# Stimulation_Stage.net
KiCad netlist of a schematic drawn in Altium Designer
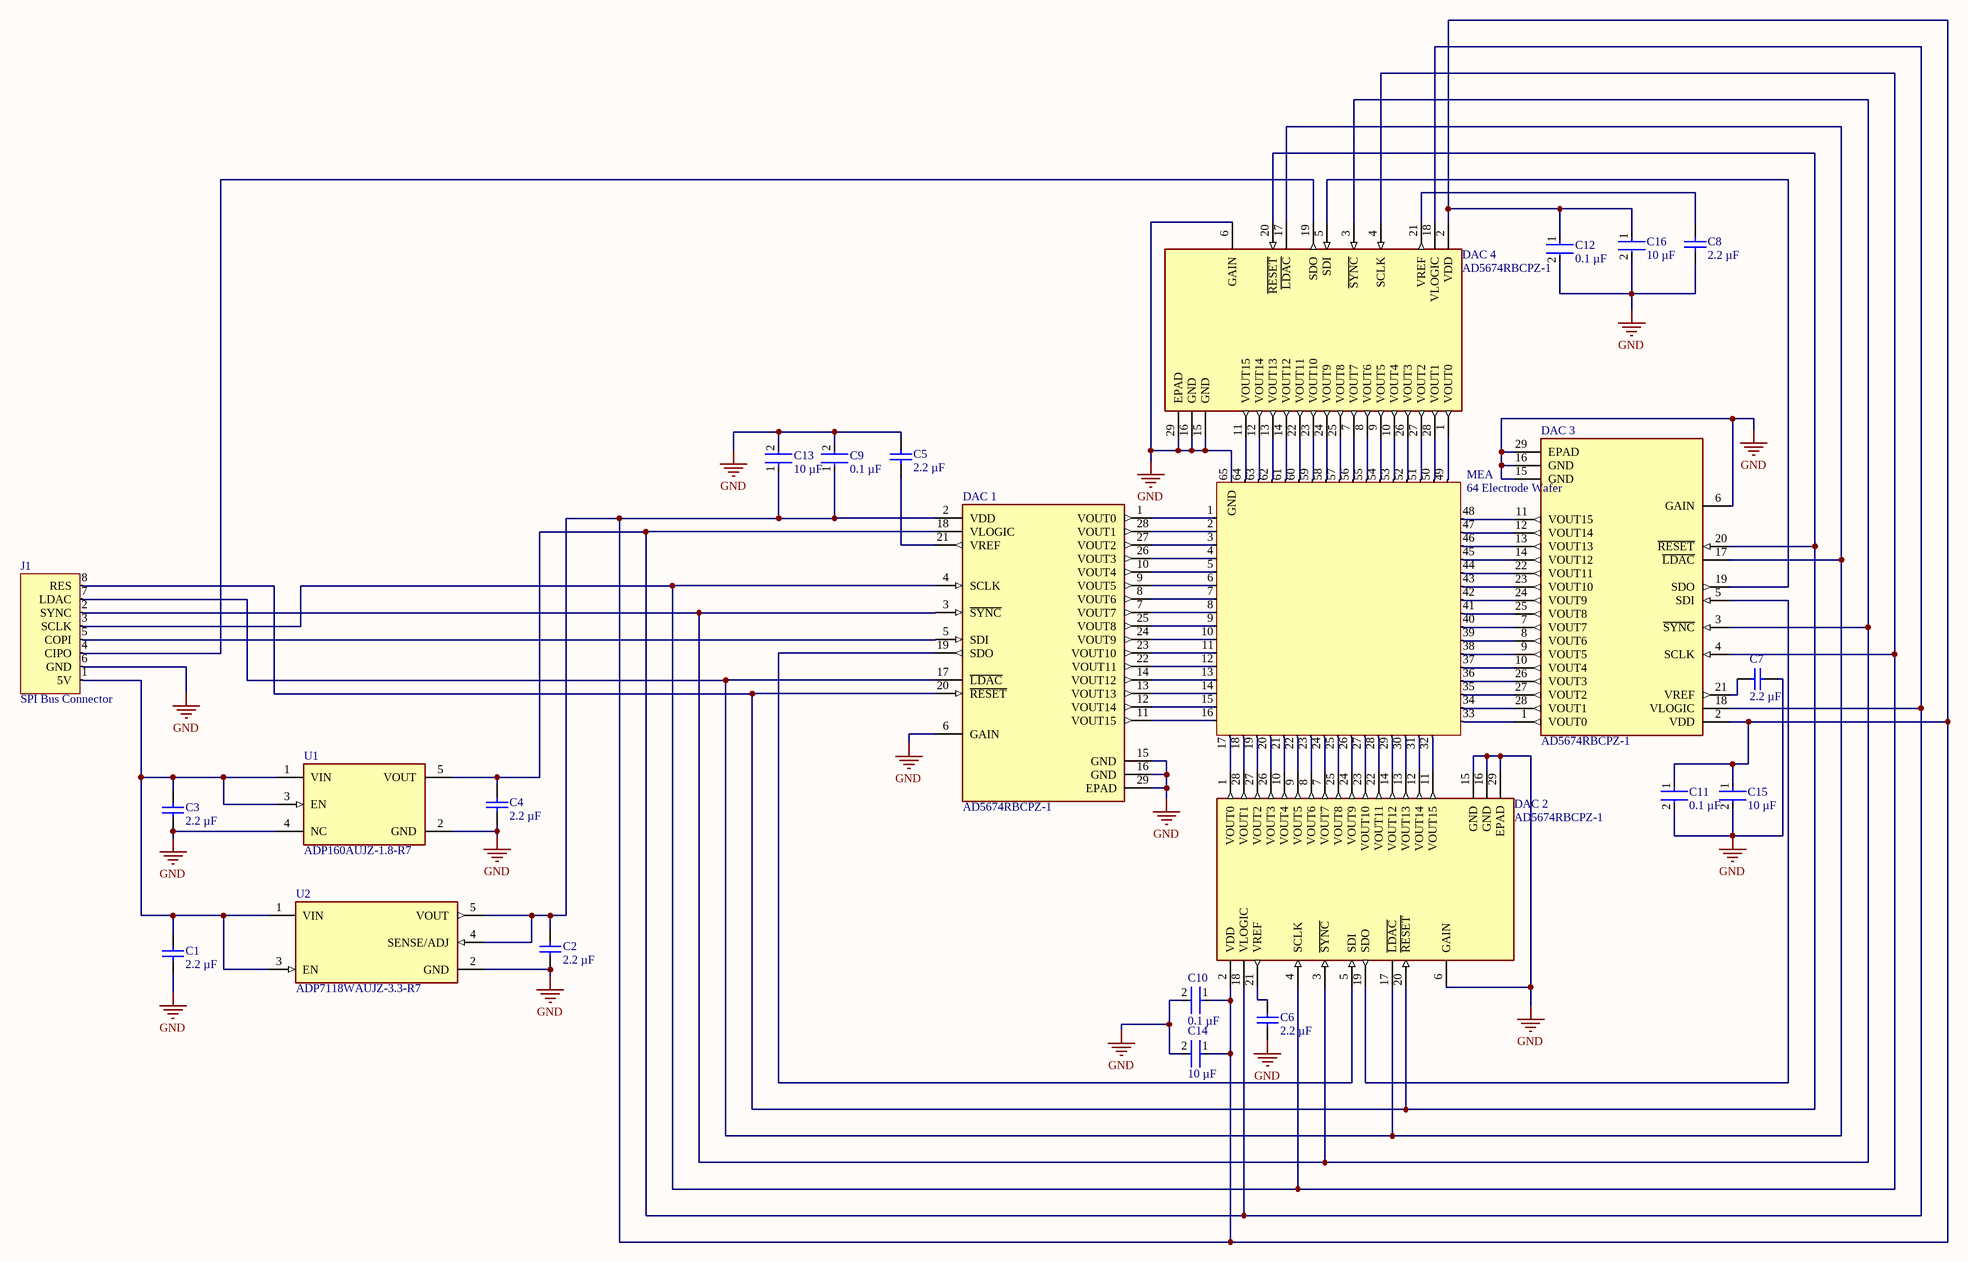
[diagram p0: Stimulation Stage.SchDoc]

(export (version "E")
  (design (tool "Eeschema 10.0.6"))
  (components
    (comp (ref "C1")
      (value "2.2 µF")
      (footprint "CAPC1608X90X30LL10T20")
      (description "Chip Capacitor, 2.2 uF, +/- 10%, 10 V, -55 to 85 degC, 0603 (1608 Metric), RoHS, Tape and Reel")
      (fields (field (name "MANUFACTURER") "Samsung Electro-Mechanics"))
      (libsource (lib "Altium Content Vault") (part "CAP-NP-2"))
    )
    (comp (ref "C2")
      (value "2.2 µF")
      (footprint "CAPC1608X90X30LL10T20")
      (description "Chip Capacitor, 2.2 uF, +/- 10%, 10 V, -55 to 85 degC, 0603 (1608 Metric), RoHS, Tape and Reel")
      (fields (field (name "MANUFACTURER") "Samsung Electro-Mechanics"))
      (libsource (lib "Altium Content Vault") (part "CAP-NP-2"))
    )
    (comp (ref "C3")
      (value "2.2 µF")
      (footprint "CAPC1608X90X30LL10T20")
      (description "Chip Capacitor, 2.2 uF, +/- 10%, 10 V, -55 to 85 degC, 0603 (1608 Metric), RoHS, Tape and Reel")
      (fields (field (name "MANUFACTURER") "Samsung Electro-Mechanics"))
      (libsource (lib "Altium Content Vault") (part "CAP-NP-2"))
    )
    (comp (ref "C4")
      (value "2.2 µF")
      (footprint "CAPC1608X90X30LL10T20")
      (description "Chip Capacitor, 2.2 uF, +/- 10%, 10 V, -55 to 85 degC, 0603 (1608 Metric), RoHS, Tape and Reel")
      (fields (field (name "MANUFACTURER") "Samsung Electro-Mechanics"))
      (libsource (lib "Altium Content Vault") (part "CAP-NP-2"))
    )
    (comp (ref "C5")
      (value "2.2 µF")
      (footprint "CAPC1608X90X30LL10T20")
      (description "Chip Capacitor, 2.2 uF, +/- 10%, 10 V, -55 to 85 degC, 0603 (1608 Metric), RoHS, Tape and Reel")
      (fields (field (name "MANUFACTURER") "Samsung Electro-Mechanics"))
      (libsource (lib "Altium Content Vault") (part "CAP-NP-2"))
    )
    (comp (ref "C6")
      (value "2.2 µF")
      (footprint "CAPC1608X90X30LL10T20")
      (description "Chip Capacitor, 2.2 uF, +/- 10%, 10 V, -55 to 85 degC, 0603 (1608 Metric), RoHS, Tape and Reel")
      (fields (field (name "MANUFACTURER") "Samsung Electro-Mechanics"))
      (libsource (lib "Altium Content Vault") (part "CAP-NP-2"))
    )
    (comp (ref "C7")
      (value "2.2 µF")
      (footprint "CAPC1608X90X30LL10T20")
      (description "Chip Capacitor, 2.2 uF, +/- 10%, 10 V, -55 to 85 degC, 0603 (1608 Metric), RoHS, Tape and Reel")
      (fields (field (name "MANUFACTURER") "Samsung Electro-Mechanics"))
      (libsource (lib "Altium Content Vault") (part "CAP-NP-2"))
    )
    (comp (ref "C8")
      (value "2.2 µF")
      (footprint "CAPC1608X90X30LL10T20")
      (description "Chip Capacitor, 2.2 uF, +/- 10%, 10 V, -55 to 85 degC, 0603 (1608 Metric), RoHS, Tape and Reel")
      (fields (field (name "MANUFACTURER") "Samsung Electro-Mechanics"))
      (libsource (lib "Altium Content Vault") (part "CAP-NP-2"))
    )
    (comp (ref "C9")
      (value "0.1 µF")
      (footprint "FP-CL278-IPC_C")
      (description "Cap Ceramic 100nF 25V X5R ±10% SMD 0402 +85°C Paper T/R")
      (fields (field (name "VOLTAGE") "25V") (field (name "TOLERANCE") "10%"))
      (libsource (lib "Altium Content Vault") (part "b4654b650e69147ec39a6b967a45e02"))
    )
    (comp (ref "C10")
      (value "0.1 µF")
      (footprint "FP-CL278-IPC_C")
      (description "Cap Ceramic 100nF 25V X5R ±10% SMD 0402 +85°C Paper T/R")
      (fields (field (name "VOLTAGE") "25V") (field (name "TOLERANCE") "10%"))
      (libsource (lib "Altium Content Vault") (part "b4654b650e69147ec39a6b967a45e02"))
    )
    (comp (ref "C11")
      (value "0.1 µF")
      (footprint "FP-CL278-IPC_C")
      (description "Cap Ceramic 100nF 25V X5R ±10% SMD 0402 +85°C Paper T/R")
      (fields (field (name "VOLTAGE") "25V") (field (name "TOLERANCE") "10%"))
      (libsource (lib "Altium Content Vault") (part "b4654b650e69147ec39a6b967a45e02"))
    )
    (comp (ref "C12")
      (value "0.1 µF")
      (footprint "FP-CL278-IPC_C")
      (description "Cap Ceramic 100nF 25V X5R ±10% SMD 0402 +85°C Paper T/R")
      (fields (field (name "VOLTAGE") "25V") (field (name "TOLERANCE") "10%"))
      (libsource (lib "Altium Content Vault") (part "b4654b650e69147ec39a6b967a45e02"))
    )
    (comp (ref "C13")
      (value "10 µF")
      (footprint "FP-CL10-IPC_C")
      (description "Cap Ceramic 10uF 6.3V X5R ±20% Pad SMD 0603 +85°C T/R")
      (fields (field (name "VOLTAGE") "6.3V") (field (name "TOLERANCE") "20%"))
      (libsource (lib "Altium Content Vault") (part "b4654b650e69147ec39a6b967a45e02"))
    )
    (comp (ref "C14")
      (value "10 µF")
      (footprint "FP-CL10-IPC_C")
      (description "Cap Ceramic 10uF 6.3V X5R ±20% Pad SMD 0603 +85°C T/R")
      (fields (field (name "VOLTAGE") "6.3V") (field (name "TOLERANCE") "20%"))
      (libsource (lib "Altium Content Vault") (part "b4654b650e69147ec39a6b967a45e02"))
    )
    (comp (ref "C15")
      (value "10 µF")
      (footprint "FP-CL10-IPC_C")
      (description "Cap Ceramic 10uF 6.3V X5R ±20% Pad SMD 0603 +85°C T/R")
      (fields (field (name "VOLTAGE") "6.3V") (field (name "TOLERANCE") "20%"))
      (libsource (lib "Altium Content Vault") (part "b4654b650e69147ec39a6b967a45e02"))
    )
    (comp (ref "C16")
      (value "10 µF")
      (footprint "FP-CL10-IPC_C")
      (description "Cap Ceramic 10uF 6.3V X5R ±20% Pad SMD 0603 +85°C T/R")
      (fields (field (name "VOLTAGE") "6.3V") (field (name "TOLERANCE") "20%"))
      (libsource (lib "Altium Content Vault") (part "b4654b650e69147ec39a6b967a45e02"))
    )
    (comp (ref "DAC 1")
      (value "AD5674RBCPZ-1")
      (footprint "FP-CP-28-9-IPC_C")
      (description "16-CH12-BITNANODAC+WITH2PPM/CREF")
      (libsource (lib "Altium Content Vault") (part "8444db3836bae7896dad1ad18e8f2a5"))
    )
    (comp (ref "DAC 2")
      (value "AD5674RBCPZ-1")
      (footprint "FP-CP-28-9-IPC_C")
      (description "16-CH12-BITNANODAC+WITH2PPM/CREF")
      (libsource (lib "") (part "8444db3836bae7896dad1ad18e8f2a5_1"))
    )
    (comp (ref "DAC 3")
      (value "AD5674RBCPZ-1")
      (footprint "FP-CP-28-9-IPC_C")
      (description "16-CH12-BITNANODAC+WITH2PPM/CREF")
      (libsource (lib "") (part "8444db3836bae7896dad1ad18e8f2a5_3"))
    )
    (comp (ref "DAC 4")
      (value "AD5674RBCPZ-1")
      (footprint "FP-CP-28-9-IPC_C")
      (description "16-CH12-BITNANODAC+WITH2PPM/CREF")
      (libsource (lib "") (part "8444db3836bae7896dad1ad18e8f2a5_2"))
    )
    (comp (ref "J1")
      (value "SPI Bus Connector")
      (footprint "SPI Bus Connector")
      (description "8 pin connector for SPI interface and power from m")
      (libsource (lib "Celestial Library Database") (part "SPI Bus Connector"))
    )
    (comp (ref "MEA")
      (value "64 Electrode Wafer")
      (footprint "64 Electrode Wafer Footprint")
      (description "64 channel transparent Microelectrode Array")
      (libsource (lib "Celestial Library Database") (part "64 Electrode Wafer"))
    )
    (comp (ref "U1")
      (value "ADP160AUJZ-1.8-R7")
      (footprint "FP-UJ-5-IPC_C")
      (description "IC REG LINEAR 1.8V 150MA TSOT5")
      (libsource (lib "Altium Content Vault") (part "49efecb8457b62bbb278fcbf558b656"))
    )
    (comp (ref "U2")
      (value "ADP7118WAUJZ-3.3-R7")
      (footprint "FP-UJ-5-IPC_C")
      (description "IC REG LINEAR 3.3V 200MA TSOT5")
      (libsource (lib "Altium Content Vault") (part "4a7971eea0f250dff842508c33254cb"))
    )
  )
  (nets
    (net (code "1") (name "GND") (class "Default")
      (node (ref "C1") (pin "1") (pinfunction "1_1") (pintype "passive"))
      (node (ref "C10") (pin "2") (pinfunction "2_2") (pintype "passive"))
      (node (ref "C11") (pin "2") (pinfunction "2_2") (pintype "passive"))
      (node (ref "C12") (pin "2") (pinfunction "2_2") (pintype "passive"))
      (node (ref "C13") (pin "2") (pinfunction "2_2") (pintype "passive"))
      (node (ref "C14") (pin "2") (pinfunction "2_2") (pintype "passive"))
      (node (ref "C15") (pin "2") (pinfunction "2_2") (pintype "passive"))
      (node (ref "C16") (pin "2") (pinfunction "2_2") (pintype "passive"))
      (node (ref "C2") (pin "1") (pinfunction "1_1") (pintype "passive"))
      (node (ref "C3") (pin "1") (pinfunction "1_1") (pintype "passive"))
      (node (ref "C4") (pin "1") (pinfunction "1_1") (pintype "passive"))
      (node (ref "C5") (pin "2") (pinfunction "2_2") (pintype "passive"))
      (node (ref "C6") (pin "1") (pinfunction "1_1") (pintype "passive"))
      (node (ref "C7") (pin "1") (pinfunction "1_1") (pintype "passive"))
      (node (ref "C8") (pin "1") (pinfunction "1_1") (pintype "passive"))
      (node (ref "C9") (pin "2") (pinfunction "2_2") (pintype "passive"))
      (node (ref "DAC 1") (pin "15") (pinfunction "GND_15") (pintype "power_in"))
      (node (ref "DAC 1") (pin "16") (pinfunction "GND_16") (pintype "power_in"))
      (node (ref "DAC 1") (pin "29") (pinfunction "EPAD_29") (pintype "power_in"))
      (node (ref "DAC 1") (pin "6") (pinfunction "GAIN_6") (pintype "passive"))
      (node (ref "DAC 2") (pin "15") (pinfunction "GND_15") (pintype "power_in"))
      (node (ref "DAC 2") (pin "16") (pinfunction "GND_16") (pintype "power_in"))
      (node (ref "DAC 2") (pin "29") (pinfunction "EPAD_29") (pintype "power_in"))
      (node (ref "DAC 2") (pin "6") (pinfunction "GAIN_6") (pintype "passive"))
      (node (ref "DAC 3") (pin "15") (pinfunction "GND_15") (pintype "power_in"))
      (node (ref "DAC 3") (pin "16") (pinfunction "GND_16") (pintype "power_in"))
      (node (ref "DAC 3") (pin "29") (pinfunction "EPAD_29") (pintype "power_in"))
      (node (ref "DAC 3") (pin "6") (pinfunction "GAIN_6") (pintype "passive"))
      (node (ref "DAC 4") (pin "15") (pinfunction "GND_15") (pintype "power_in"))
      (node (ref "DAC 4") (pin "16") (pinfunction "GND_16") (pintype "power_in"))
      (node (ref "DAC 4") (pin "29") (pinfunction "EPAD_29") (pintype "power_in"))
      (node (ref "DAC 4") (pin "6") (pinfunction "GAIN_6") (pintype "passive"))
      (node (ref "J1") (pin "6") (pinfunction "GND_6") (pintype "power_in"))
      (node (ref "MEA") (pin "65") (pinfunction "GND_65") (pintype "input"))
      (node (ref "U1") (pin "2") (pinfunction "GND_2") (pintype "power_in"))
      (node (ref "U1") (pin "4") (pinfunction "NC_4") (pintype "passive"))
      (node (ref "U2") (pin "2") (pinfunction "GND_2") (pintype "power_in"))
    )
    (net (code "2") (name "Net-(DAC 1-SCLK)") (class "Default")
      (node (ref "DAC 1") (pin "4") (pinfunction "SCLK_4") (pintype "input"))
      (node (ref "DAC 2") (pin "4") (pinfunction "SCLK_4") (pintype "input"))
      (node (ref "DAC 3") (pin "4") (pinfunction "SCLK_4") (pintype "input"))
      (node (ref "DAC 4") (pin "4") (pinfunction "SCLK_4") (pintype "input"))
      (node (ref "J1") (pin "3") (pinfunction "SCLK_3") (pintype "output"))
    )
    (net (code "3") (name "Net-(DAC 1-SDI)") (class "Default")
      (node (ref "DAC 1") (pin "5") (pinfunction "SDI_5") (pintype "input"))
      (node (ref "J1") (pin "5") (pinfunction "COPI_5") (pintype "output"))
    )
    (net (code "4") (name "Net-(DAC 1-SDO)") (class "Default")
      (node (ref "DAC 1") (pin "19") (pinfunction "SDO_19") (pintype "output"))
      (node (ref "DAC 2") (pin "5") (pinfunction "SDI_5") (pintype "input"))
    )
    (net (code "5") (name "Net-(DAC 1-VDD)") (class "Default")
      (node (ref "C10") (pin "1") (pinfunction "1_1") (pintype "passive"))
      (node (ref "C11") (pin "1") (pinfunction "1_1") (pintype "passive"))
      (node (ref "C12") (pin "1") (pinfunction "1_1") (pintype "passive"))
      (node (ref "C13") (pin "1") (pinfunction "1_1") (pintype "passive"))
      (node (ref "C14") (pin "1") (pinfunction "1_1") (pintype "passive"))
      (node (ref "C15") (pin "1") (pinfunction "1_1") (pintype "passive"))
      (node (ref "C16") (pin "1") (pinfunction "1_1") (pintype "passive"))
      (node (ref "C2") (pin "2") (pinfunction "2_2") (pintype "passive"))
      (node (ref "C9") (pin "1") (pinfunction "1_1") (pintype "passive"))
      (node (ref "DAC 1") (pin "2") (pinfunction "VDD_2") (pintype "power_in"))
      (node (ref "DAC 2") (pin "2") (pinfunction "VDD_2") (pintype "power_in"))
      (node (ref "DAC 3") (pin "2") (pinfunction "VDD_2") (pintype "power_in"))
      (node (ref "DAC 4") (pin "2") (pinfunction "VDD_2") (pintype "power_in"))
      (node (ref "U2") (pin "4") (pinfunction "SENSE/ADJ_4") (pintype "input"))
      (node (ref "U2") (pin "5") (pinfunction "VOUT_5") (pintype "output"))
    )
    (net (code "6") (name "Net-(DAC 1-VLOGIC)") (class "Default")
      (node (ref "C4") (pin "2") (pinfunction "2_2") (pintype "passive"))
      (node (ref "DAC 1") (pin "18") (pinfunction "VLOGIC_18") (pintype "power_in"))
      (node (ref "DAC 2") (pin "18") (pinfunction "VLOGIC_18") (pintype "power_in"))
      (node (ref "DAC 3") (pin "18") (pinfunction "VLOGIC_18") (pintype "power_in"))
      (node (ref "DAC 4") (pin "18") (pinfunction "VLOGIC_18") (pintype "power_in"))
      (node (ref "U1") (pin "5") (pinfunction "VOUT_5") (pintype "power_in"))
    )
    (net (code "7") (name "Net-(DAC 1-VOUT0)") (class "Default")
      (node (ref "DAC 1") (pin "1") (pinfunction "VOUT0_1") (pintype "output"))
      (node (ref "MEA") (pin "1") (pintype "input"))
    )
    (net (code "8") (name "Net-(DAC 1-VOUT1)") (class "Default")
      (node (ref "DAC 1") (pin "28") (pinfunction "VOUT1_28") (pintype "output"))
      (node (ref "MEA") (pin "2") (pintype "input"))
    )
    (net (code "9") (name "Net-(DAC 1-VOUT2)") (class "Default")
      (node (ref "DAC 1") (pin "27") (pinfunction "VOUT2_27") (pintype "output"))
      (node (ref "MEA") (pin "3") (pintype "input"))
    )
    (net (code "10") (name "Net-(DAC 1-VOUT3)") (class "Default")
      (node (ref "DAC 1") (pin "26") (pinfunction "VOUT3_26") (pintype "output"))
      (node (ref "MEA") (pin "4") (pintype "input"))
    )
    (net (code "11") (name "Net-(DAC 1-VOUT4)") (class "Default")
      (node (ref "DAC 1") (pin "10") (pinfunction "VOUT4_10") (pintype "output"))
      (node (ref "MEA") (pin "5") (pintype "input"))
    )
    (net (code "12") (name "Net-(DAC 1-VOUT5)") (class "Default")
      (node (ref "DAC 1") (pin "9") (pinfunction "VOUT5_9") (pintype "output"))
      (node (ref "MEA") (pin "6") (pintype "input"))
    )
    (net (code "13") (name "Net-(DAC 1-VOUT6)") (class "Default")
      (node (ref "DAC 1") (pin "8") (pinfunction "VOUT6_8") (pintype "output"))
      (node (ref "MEA") (pin "7") (pintype "input"))
    )
    (net (code "14") (name "Net-(DAC 1-VOUT7)") (class "Default")
      (node (ref "DAC 1") (pin "7") (pinfunction "VOUT7_7") (pintype "output"))
      (node (ref "MEA") (pin "8") (pintype "input"))
    )
    (net (code "15") (name "Net-(DAC 1-VOUT8)") (class "Default")
      (node (ref "DAC 1") (pin "25") (pinfunction "VOUT8_25") (pintype "output"))
      (node (ref "MEA") (pin "9") (pintype "input"))
    )
    (net (code "16") (name "Net-(DAC 1-VOUT9)") (class "Default")
      (node (ref "DAC 1") (pin "24") (pinfunction "VOUT9_24") (pintype "output"))
      (node (ref "MEA") (pin "10") (pintype "input"))
    )
    (net (code "17") (name "Net-(DAC 1-VOUT10)") (class "Default")
      (node (ref "DAC 1") (pin "23") (pinfunction "VOUT10_23") (pintype "output"))
      (node (ref "MEA") (pin "11") (pintype "input"))
    )
    (net (code "18") (name "Net-(DAC 1-VOUT11)") (class "Default")
      (node (ref "DAC 1") (pin "22") (pinfunction "VOUT11_22") (pintype "output"))
      (node (ref "MEA") (pin "12") (pintype "input"))
    )
    (net (code "19") (name "Net-(DAC 1-VOUT12)") (class "Default")
      (node (ref "DAC 1") (pin "14") (pinfunction "VOUT12_14") (pintype "output"))
      (node (ref "MEA") (pin "13") (pintype "input"))
    )
    (net (code "20") (name "Net-(DAC 1-VOUT13)") (class "Default")
      (node (ref "DAC 1") (pin "13") (pinfunction "VOUT13_13") (pintype "output"))
      (node (ref "MEA") (pin "14") (pintype "input"))
    )
    (net (code "21") (name "Net-(DAC 1-VOUT14)") (class "Default")
      (node (ref "DAC 1") (pin "12") (pinfunction "VOUT14_12") (pintype "output"))
      (node (ref "MEA") (pin "15") (pintype "input"))
    )
    (net (code "22") (name "Net-(DAC 1-VOUT15)") (class "Default")
      (node (ref "DAC 1") (pin "11") (pinfunction "VOUT15_11") (pintype "output"))
      (node (ref "MEA") (pin "16") (pintype "input"))
    )
    (net (code "23") (name "Net-(DAC 1-VREF)") (class "Default")
      (node (ref "C5") (pin "1") (pinfunction "1_1") (pintype "passive"))
      (node (ref "DAC 1") (pin "21") (pinfunction "VREF_21") (pintype "output"))
    )
    (net (code "24") (name "Net-(DAC 1-~{LDAC})") (class "Default")
      (node (ref "DAC 1") (pin "17") (pinfunction "~{LDAC}_17") (pintype "passive"))
      (node (ref "DAC 2") (pin "17") (pinfunction "~{LDAC}_17") (pintype "passive"))
      (node (ref "DAC 3") (pin "17") (pinfunction "~{LDAC}_17") (pintype "passive"))
      (node (ref "DAC 4") (pin "17") (pinfunction "~{LDAC}_17") (pintype "passive"))
      (node (ref "J1") (pin "7") (pinfunction "LDAC_7") (pintype "output"))
    )
    (net (code "25") (name "Net-(DAC 1-~{RESET})") (class "Default")
      (node (ref "DAC 1") (pin "20") (pinfunction "~{RESET}_20") (pintype "input"))
      (node (ref "DAC 2") (pin "20") (pinfunction "~{RESET}_20") (pintype "input"))
      (node (ref "DAC 3") (pin "20") (pinfunction "~{RESET}_20") (pintype "input"))
      (node (ref "DAC 4") (pin "20") (pinfunction "~{RESET}_20") (pintype "input"))
      (node (ref "J1") (pin "8") (pinfunction "RES_8") (pintype "output"))
    )
    (net (code "26") (name "Net-(DAC 1-~{SYNC})") (class "Default")
      (node (ref "DAC 1") (pin "3") (pinfunction "~{SYNC}_3") (pintype "input"))
      (node (ref "DAC 2") (pin "3") (pinfunction "~{SYNC}_3") (pintype "input"))
      (node (ref "DAC 3") (pin "3") (pinfunction "~{SYNC}_3") (pintype "input"))
      (node (ref "DAC 4") (pin "3") (pinfunction "~{SYNC}_3") (pintype "input"))
      (node (ref "J1") (pin "2") (pinfunction "SYNC_2") (pintype "output"))
    )
    (net (code "27") (name "Net-(DAC 2-SDO)") (class "Default")
      (node (ref "DAC 2") (pin "19") (pinfunction "SDO_19") (pintype "output"))
      (node (ref "DAC 3") (pin "5") (pinfunction "SDI_5") (pintype "input"))
    )
    (net (code "28") (name "Net-(DAC 2-VOUT0)") (class "Default")
      (node (ref "DAC 2") (pin "1") (pinfunction "VOUT0_1") (pintype "output"))
      (node (ref "MEA") (pin "17") (pintype "input"))
    )
    (net (code "29") (name "Net-(DAC 2-VOUT1)") (class "Default")
      (node (ref "DAC 2") (pin "28") (pinfunction "VOUT1_28") (pintype "output"))
      (node (ref "MEA") (pin "18") (pintype "input"))
    )
    (net (code "30") (name "Net-(DAC 2-VOUT2)") (class "Default")
      (node (ref "DAC 2") (pin "27") (pinfunction "VOUT2_27") (pintype "output"))
      (node (ref "MEA") (pin "19") (pintype "input"))
    )
    (net (code "31") (name "Net-(DAC 2-VOUT3)") (class "Default")
      (node (ref "DAC 2") (pin "26") (pinfunction "VOUT3_26") (pintype "output"))
      (node (ref "MEA") (pin "20") (pintype "input"))
    )
    (net (code "32") (name "Net-(DAC 2-VOUT4)") (class "Default")
      (node (ref "DAC 2") (pin "10") (pinfunction "VOUT4_10") (pintype "output"))
      (node (ref "MEA") (pin "21") (pintype "input"))
    )
    (net (code "33") (name "Net-(DAC 2-VOUT5)") (class "Default")
      (node (ref "DAC 2") (pin "9") (pinfunction "VOUT5_9") (pintype "output"))
      (node (ref "MEA") (pin "22") (pintype "input"))
    )
    (net (code "34") (name "Net-(DAC 2-VOUT6)") (class "Default")
      (node (ref "DAC 2") (pin "8") (pinfunction "VOUT6_8") (pintype "output"))
      (node (ref "MEA") (pin "23") (pintype "input"))
    )
    (net (code "35") (name "Net-(DAC 2-VOUT7)") (class "Default")
      (node (ref "DAC 2") (pin "7") (pinfunction "VOUT7_7") (pintype "output"))
      (node (ref "MEA") (pin "24") (pintype "input"))
    )
    (net (code "36") (name "Net-(DAC 2-VOUT8)") (class "Default")
      (node (ref "DAC 2") (pin "25") (pinfunction "VOUT8_25") (pintype "output"))
      (node (ref "MEA") (pin "25") (pintype "input"))
    )
    (net (code "37") (name "Net-(DAC 2-VOUT9)") (class "Default")
      (node (ref "DAC 2") (pin "24") (pinfunction "VOUT9_24") (pintype "output"))
      (node (ref "MEA") (pin "26") (pintype "input"))
    )
    (net (code "38") (name "Net-(DAC 2-VOUT10)") (class "Default")
      (node (ref "DAC 2") (pin "23") (pinfunction "VOUT10_23") (pintype "output"))
      (node (ref "MEA") (pin "27") (pintype "input"))
    )
    (net (code "39") (name "Net-(DAC 2-VOUT11)") (class "Default")
      (node (ref "DAC 2") (pin "22") (pinfunction "VOUT11_22") (pintype "output"))
      (node (ref "MEA") (pin "28") (pintype "input"))
    )
    (net (code "40") (name "Net-(DAC 2-VOUT12)") (class "Default")
      (node (ref "DAC 2") (pin "14") (pinfunction "VOUT12_14") (pintype "output"))
      (node (ref "MEA") (pin "29") (pintype "input"))
    )
    (net (code "41") (name "Net-(DAC 2-VOUT13)") (class "Default")
      (node (ref "DAC 2") (pin "13") (pinfunction "VOUT13_13") (pintype "output"))
      (node (ref "MEA") (pin "30") (pintype "input"))
    )
    (net (code "42") (name "Net-(DAC 2-VOUT14)") (class "Default")
      (node (ref "DAC 2") (pin "12") (pinfunction "VOUT14_12") (pintype "output"))
      (node (ref "MEA") (pin "31") (pintype "input"))
    )
    (net (code "43") (name "Net-(DAC 2-VOUT15)") (class "Default")
      (node (ref "DAC 2") (pin "11") (pinfunction "VOUT15_11") (pintype "output"))
      (node (ref "MEA") (pin "32") (pintype "input"))
    )
    (net (code "44") (name "Net-(DAC 2-VREF)") (class "Default")
      (node (ref "C6") (pin "2") (pinfunction "2_2") (pintype "passive"))
      (node (ref "DAC 2") (pin "21") (pinfunction "VREF_21") (pintype "output"))
    )
    (net (code "45") (name "Net-(DAC 3-SDO)") (class "Default")
      (node (ref "DAC 3") (pin "19") (pinfunction "SDO_19") (pintype "output"))
      (node (ref "DAC 4") (pin "5") (pinfunction "SDI_5") (pintype "input"))
    )
    (net (code "46") (name "Net-(DAC 3-VOUT0)") (class "Default")
      (node (ref "DAC 3") (pin "1") (pinfunction "VOUT0_1") (pintype "output"))
      (node (ref "MEA") (pin "33") (pintype "input"))
    )
    (net (code "47") (name "Net-(DAC 3-VOUT1)") (class "Default")
      (node (ref "DAC 3") (pin "28") (pinfunction "VOUT1_28") (pintype "output"))
      (node (ref "MEA") (pin "34") (pintype "input"))
    )
    (net (code "48") (name "Net-(DAC 3-VOUT2)") (class "Default")
      (node (ref "DAC 3") (pin "27") (pinfunction "VOUT2_27") (pintype "output"))
      (node (ref "MEA") (pin "35") (pintype "input"))
    )
    (net (code "49") (name "Net-(DAC 3-VOUT3)") (class "Default")
      (node (ref "DAC 3") (pin "26") (pinfunction "VOUT3_26") (pintype "output"))
      (node (ref "MEA") (pin "36") (pintype "input"))
    )
    (net (code "50") (name "Net-(DAC 3-VOUT4)") (class "Default")
      (node (ref "DAC 3") (pin "10") (pinfunction "VOUT4_10") (pintype "output"))
      (node (ref "MEA") (pin "37") (pintype "input"))
    )
    (net (code "51") (name "Net-(DAC 3-VOUT5)") (class "Default")
      (node (ref "DAC 3") (pin "9") (pinfunction "VOUT5_9") (pintype "output"))
      (node (ref "MEA") (pin "38") (pintype "input"))
    )
    (net (code "52") (name "Net-(DAC 3-VOUT6)") (class "Default")
      (node (ref "DAC 3") (pin "8") (pinfunction "VOUT6_8") (pintype "output"))
      (node (ref "MEA") (pin "39") (pintype "input"))
    )
    (net (code "53") (name "Net-(DAC 3-VOUT7)") (class "Default")
      (node (ref "DAC 3") (pin "7") (pinfunction "VOUT7_7") (pintype "output"))
      (node (ref "MEA") (pin "40") (pintype "input"))
    )
    (net (code "54") (name "Net-(DAC 3-VOUT8)") (class "Default")
      (node (ref "DAC 3") (pin "25") (pinfunction "VOUT8_25") (pintype "output"))
      (node (ref "MEA") (pin "41") (pintype "input"))
    )
    (net (code "55") (name "Net-(DAC 3-VOUT9)") (class "Default")
      (node (ref "DAC 3") (pin "24") (pinfunction "VOUT9_24") (pintype "output"))
      (node (ref "MEA") (pin "42") (pintype "input"))
    )
    (net (code "56") (name "Net-(DAC 3-VOUT10)") (class "Default")
      (node (ref "DAC 3") (pin "23") (pinfunction "VOUT10_23") (pintype "output"))
      (node (ref "MEA") (pin "43") (pintype "input"))
    )
    (net (code "57") (name "Net-(DAC 3-VOUT11)") (class "Default")
      (node (ref "DAC 3") (pin "22") (pinfunction "VOUT11_22") (pintype "output"))
      (node (ref "MEA") (pin "44") (pintype "input"))
    )
    (net (code "58") (name "Net-(DAC 3-VOUT12)") (class "Default")
      (node (ref "DAC 3") (pin "14") (pinfunction "VOUT12_14") (pintype "output"))
      (node (ref "MEA") (pin "45") (pintype "input"))
    )
    (net (code "59") (name "Net-(DAC 3-VOUT13)") (class "Default")
      (node (ref "DAC 3") (pin "13") (pinfunction "VOUT13_13") (pintype "output"))
      (node (ref "MEA") (pin "46") (pintype "input"))
    )
    (net (code "60") (name "Net-(DAC 3-VOUT14)") (class "Default")
      (node (ref "DAC 3") (pin "12") (pinfunction "VOUT14_12") (pintype "output"))
      (node (ref "MEA") (pin "47") (pintype "input"))
    )
    (net (code "61") (name "Net-(DAC 3-VOUT15)") (class "Default")
      (node (ref "DAC 3") (pin "11") (pinfunction "VOUT15_11") (pintype "output"))
      (node (ref "MEA") (pin "48") (pintype "input"))
    )
    (net (code "62") (name "Net-(DAC 3-VREF)") (class "Default")
      (node (ref "C7") (pin "2") (pinfunction "2_2") (pintype "passive"))
      (node (ref "DAC 3") (pin "21") (pinfunction "VREF_21") (pintype "output"))
    )
    (net (code "63") (name "Net-(DAC 4-SDO)") (class "Default")
      (node (ref "DAC 4") (pin "19") (pinfunction "SDO_19") (pintype "output"))
      (node (ref "J1") (pin "4") (pinfunction "CIPO_4") (pintype "input"))
    )
    (net (code "64") (name "Net-(DAC 4-VOUT0)") (class "Default")
      (node (ref "DAC 4") (pin "1") (pinfunction "VOUT0_1") (pintype "output"))
      (node (ref "MEA") (pin "49") (pintype "input"))
    )
    (net (code "65") (name "Net-(DAC 4-VOUT1)") (class "Default")
      (node (ref "DAC 4") (pin "28") (pinfunction "VOUT1_28") (pintype "output"))
      (node (ref "MEA") (pin "50") (pintype "input"))
    )
    (net (code "66") (name "Net-(DAC 4-VOUT2)") (class "Default")
      (node (ref "DAC 4") (pin "27") (pinfunction "VOUT2_27") (pintype "output"))
      (node (ref "MEA") (pin "51") (pintype "input"))
    )
    (net (code "67") (name "Net-(DAC 4-VOUT3)") (class "Default")
      (node (ref "DAC 4") (pin "26") (pinfunction "VOUT3_26") (pintype "output"))
      (node (ref "MEA") (pin "52") (pintype "input"))
    )
    (net (code "68") (name "Net-(DAC 4-VOUT4)") (class "Default")
      (node (ref "DAC 4") (pin "10") (pinfunction "VOUT4_10") (pintype "output"))
      (node (ref "MEA") (pin "53") (pintype "input"))
    )
    (net (code "69") (name "Net-(DAC 4-VOUT5)") (class "Default")
      (node (ref "DAC 4") (pin "9") (pinfunction "VOUT5_9") (pintype "output"))
      (node (ref "MEA") (pin "54") (pintype "input"))
    )
    (net (code "70") (name "Net-(DAC 4-VOUT6)") (class "Default")
      (node (ref "DAC 4") (pin "8") (pinfunction "VOUT6_8") (pintype "output"))
      (node (ref "MEA") (pin "55") (pintype "input"))
    )
    (net (code "71") (name "Net-(DAC 4-VOUT7)") (class "Default")
      (node (ref "DAC 4") (pin "7") (pinfunction "VOUT7_7") (pintype "output"))
      (node (ref "MEA") (pin "56") (pintype "input"))
    )
    (net (code "72") (name "Net-(DAC 4-VOUT8)") (class "Default")
      (node (ref "DAC 4") (pin "25") (pinfunction "VOUT8_25") (pintype "output"))
      (node (ref "MEA") (pin "57") (pintype "input"))
    )
    (net (code "73") (name "Net-(DAC 4-VOUT9)") (class "Default")
      (node (ref "DAC 4") (pin "24") (pinfunction "VOUT9_24") (pintype "output"))
      (node (ref "MEA") (pin "58") (pintype "input"))
    )
    (net (code "74") (name "Net-(DAC 4-VOUT10)") (class "Default")
      (node (ref "DAC 4") (pin "23") (pinfunction "VOUT10_23") (pintype "output"))
      (node (ref "MEA") (pin "59") (pintype "input"))
    )
    (net (code "75") (name "Net-(DAC 4-VOUT11)") (class "Default")
      (node (ref "DAC 4") (pin "22") (pinfunction "VOUT11_22") (pintype "output"))
      (node (ref "MEA") (pin "60") (pintype "input"))
    )
    (net (code "76") (name "Net-(DAC 4-VOUT12)") (class "Default")
      (node (ref "DAC 4") (pin "14") (pinfunction "VOUT12_14") (pintype "output"))
      (node (ref "MEA") (pin "61") (pintype "input"))
    )
    (net (code "77") (name "Net-(DAC 4-VOUT13)") (class "Default")
      (node (ref "DAC 4") (pin "13") (pinfunction "VOUT13_13") (pintype "output"))
      (node (ref "MEA") (pin "62") (pintype "input"))
    )
    (net (code "78") (name "Net-(DAC 4-VOUT14)") (class "Default")
      (node (ref "DAC 4") (pin "12") (pinfunction "VOUT14_12") (pintype "output"))
      (node (ref "MEA") (pin "63") (pintype "input"))
    )
    (net (code "79") (name "Net-(DAC 4-VOUT15)") (class "Default")
      (node (ref "DAC 4") (pin "11") (pinfunction "VOUT15_11") (pintype "output"))
      (node (ref "MEA") (pin "64") (pintype "input"))
    )
    (net (code "80") (name "Net-(DAC 4-VREF)") (class "Default")
      (node (ref "C8") (pin "2") (pinfunction "2_2") (pintype "passive"))
      (node (ref "DAC 4") (pin "21") (pinfunction "VREF_21") (pintype "output"))
    )
    (net (code "81") (name "Net-(J1-5V)") (class "Default")
      (node (ref "C1") (pin "2") (pinfunction "2_2") (pintype "passive"))
      (node (ref "C3") (pin "2") (pinfunction "2_2") (pintype "passive"))
      (node (ref "J1") (pin "1") (pinfunction "5V_1") (pintype "power_in"))
      (node (ref "U1") (pin "1") (pinfunction "VIN_1") (pintype "power_in"))
      (node (ref "U1") (pin "3") (pinfunction "EN_3") (pintype "input"))
      (node (ref "U2") (pin "1") (pinfunction "VIN_1") (pintype "power_in"))
      (node (ref "U2") (pin "3") (pinfunction "EN_3") (pintype "input"))
    )
  )
)
